# I2C_switch.net
KiCad netlist of a schematic drawn in Altium Designer
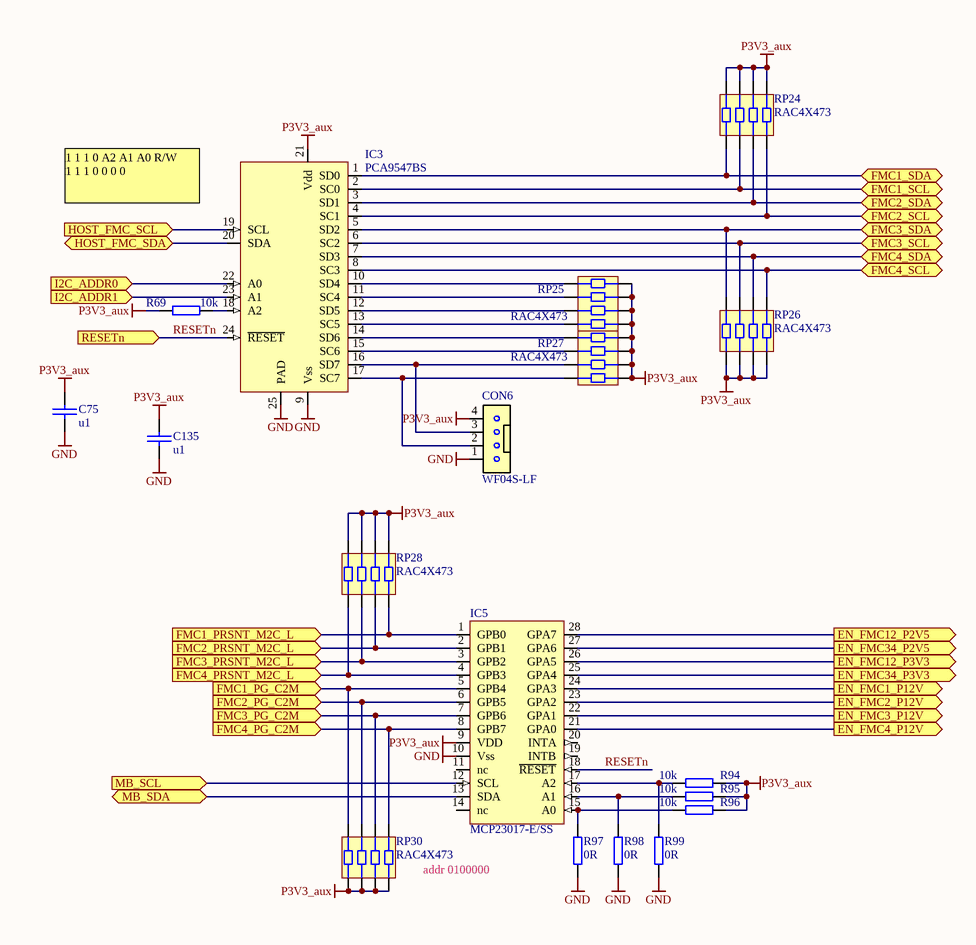
[diagram p0: I2C switch.SchDoc]

(export (version "E")
  (design (tool "Eeschema 10.0.6"))
  (components
    (comp (ref "C75")
      (value "u1")
      (footprint "0402C")
      (description "Capacitor SMD")
      (libsource (lib "LIBRARY_SCH") (part "CAP_SMD"))
    )
    (comp (ref "C135")
      (value "u1")
      (footprint "0402C")
      (description "Capacitor SMD")
      (libsource (lib "LIBRARY_SCH") (part "CAP_SMD"))
    )
    (comp (ref "CON6")
      (value "WF04S-LF")
      (footprint "CON_WF04S-LF")
      (libsource (lib "LIBRARY_SCH") (part "CON_4_2.54_key"))
    )
    (comp (ref "IC3")
      (value "PCA9547BS")
      (footprint "HVQFN24")
      (description "8-channel I2C-bus multiplexer with reset")
      (libsource (lib "LIBRARY_SCH") (part "IIC_MUX_PCA9547"))
    )
    (comp (ref "IC5")
      (value "MCP23017-E/SS")
      (footprint "SSOP28")
      (description "16 bit I2C expander")
      (libsource (lib "LIBRARY_SCH") (part "IIC_MCP23017"))
    )
    (comp (ref "R69")
      (value "10k")
      (footprint "0402R")
      (description "SMD Resistor")
      (libsource (lib "LIBRARY_SCH") (part "RES_0402"))
    )
    (comp (ref "R94")
      (value "10k")
      (footprint "0402R")
      (description "SMD Resistor")
      (libsource (lib "LIBRARY_SCH") (part "RES_0603"))
    )
    (comp (ref "R95")
      (value "10k")
      (footprint "0402R")
      (description "SMD Resistor")
      (libsource (lib "LIBRARY_SCH") (part "RES_0603"))
    )
    (comp (ref "R96")
      (value "10k")
      (footprint "0402R")
      (description "SMD Resistor")
      (libsource (lib "LIBRARY_SCH") (part "RES_0603"))
    )
    (comp (ref "R97")
      (value "0R")
      (footprint "0603R")
      (description "SMD Resistor")
      (libsource (lib "LIBRARY_SCH") (part "RES_0402"))
    )
    (comp (ref "R98")
      (value "0R")
      (footprint "0603R")
      (description "SMD Resistor")
      (libsource (lib "LIBRARY_SCH") (part "RES_0402"))
    )
    (comp (ref "R99")
      (value "0R")
      (footprint "0603R")
      (description "SMD Resistor")
      (libsource (lib "LIBRARY_SCH") (part "RES_0402"))
    )
    (comp (ref "RP24")
      (value "RAC4X473")
      (footprint "CAY-16")
      (description "Resistor network 1206 (4x0402) Maritex RAC4Xxxx")
      (libsource (lib "*") (part "RES_ARRAY_1206"))
    )
    (comp (ref "RP25")
      (value "RAC4X473")
      (footprint "CAY-16")
      (description "Resistor network 1206 (4x0402) Maritex RAC4Xxxx")
      (libsource (lib "") (part "RES_ARRAY_1206_1"))
    )
    (comp (ref "RP26")
      (value "RAC4X473")
      (footprint "CAY-16")
      (description "Resistor network 1206 (4x0402) Maritex RAC4Xxxx")
      (libsource (lib "") (part "RES_ARRAY_1206_1"))
    )
    (comp (ref "RP27")
      (value "RAC4X473")
      (footprint "CAY-16")
      (description "Resistor network 1206 (4x0402) Maritex RAC4Xxxx")
      (libsource (lib "") (part "RES_ARRAY_1206_1"))
    )
    (comp (ref "RP28")
      (value "RAC4X473")
      (footprint "CAY-16")
      (description "Resistor network 1206 (4x0402) Maritex RAC4Xxxx")
      (libsource (lib "") (part "RES_ARRAY_1206_1"))
    )
    (comp (ref "RP30")
      (value "RAC4X473")
      (footprint "CAY-16")
      (description "Resistor network 1206 (4x0402) Maritex RAC4Xxxx")
      (libsource (lib "") (part "RES_ARRAY_1206_2"))
    )
  )
  (nets
    (net (code "1") (name "/EN_FMC1_P12V") (class "Default")
      (node (ref "IC5") (pin "24") (pinfunction "GPA3_24") (pintype "bidirectional"))
    )
    (net (code "2") (name "/EN_FMC2_P12V") (class "Default")
      (node (ref "IC5") (pin "23") (pinfunction "GPA2_23") (pintype "bidirectional"))
    )
    (net (code "3") (name "/EN_FMC3_P12V") (class "Default")
      (node (ref "IC5") (pin "22") (pinfunction "GPA1_22") (pintype "bidirectional"))
    )
    (net (code "4") (name "/EN_FMC4_P12V") (class "Default")
      (node (ref "IC5") (pin "21") (pinfunction "GPA0_21") (pintype "bidirectional"))
    )
    (net (code "5") (name "/EN_FMC12_P2V5") (class "Default")
      (node (ref "IC5") (pin "28") (pinfunction "GPA7_28") (pintype "bidirectional"))
    )
    (net (code "6") (name "/EN_FMC12_P3V3") (class "Default")
      (node (ref "IC5") (pin "26") (pinfunction "GPA5_26") (pintype "bidirectional"))
    )
    (net (code "7") (name "/EN_FMC34_P2V5") (class "Default")
      (node (ref "IC5") (pin "27") (pinfunction "GPA6_27") (pintype "bidirectional"))
    )
    (net (code "8") (name "/EN_FMC34_P3V3") (class "Default")
      (node (ref "IC5") (pin "25") (pinfunction "GPA4_25") (pintype "bidirectional"))
    )
    (net (code "9") (name "/FMC1_PG_C2M") (class "Default")
      (node (ref "IC5") (pin "5") (pinfunction "GPB4_5") (pintype "bidirectional"))
      (node (ref "RP30") (pin "4") (pinfunction "4_4") (pintype "passive"))
    )
    (net (code "10") (name "/FMC1_PRSNT_M2C_L") (class "Default")
      (node (ref "IC5") (pin "1") (pinfunction "GPB0_1") (pintype "bidirectional"))
      (node (ref "RP28") (pin "4") (pinfunction "4_4") (pintype "passive"))
    )
    (net (code "11") (name "/FMC1_SCL") (class "Default")
      (node (ref "IC3") (pin "2") (pinfunction "SC0_2") (pintype "bidirectional"))
      (node (ref "RP24") (pin "7") (pinfunction "7_7") (pintype "passive"))
    )
    (net (code "12") (name "/FMC1_SDA") (class "Default")
      (node (ref "IC3") (pin "1") (pinfunction "SD0_1") (pintype "bidirectional"))
      (node (ref "RP24") (pin "8") (pinfunction "8_8") (pintype "passive"))
    )
    (net (code "13") (name "/FMC2_PG_C2M") (class "Default")
      (node (ref "IC5") (pin "6") (pinfunction "GPB5_6") (pintype "bidirectional"))
      (node (ref "RP30") (pin "3") (pinfunction "3_3") (pintype "passive"))
    )
    (net (code "14") (name "/FMC2_PRSNT_M2C_L") (class "Default")
      (node (ref "IC5") (pin "2") (pinfunction "GPB1_2") (pintype "bidirectional"))
      (node (ref "RP28") (pin "3") (pinfunction "3_3") (pintype "passive"))
    )
    (net (code "15") (name "/FMC2_SCL") (class "Default")
      (node (ref "IC3") (pin "4") (pinfunction "SC1_4") (pintype "bidirectional"))
      (node (ref "RP24") (pin "5") (pinfunction "5_5") (pintype "passive"))
    )
    (net (code "16") (name "/FMC2_SDA") (class "Default")
      (node (ref "IC3") (pin "3") (pinfunction "SD1_3") (pintype "bidirectional"))
      (node (ref "RP24") (pin "6") (pinfunction "6_6") (pintype "passive"))
    )
    (net (code "17") (name "/FMC3_PG_C2M") (class "Default")
      (node (ref "IC5") (pin "7") (pinfunction "GPB6_7") (pintype "bidirectional"))
      (node (ref "RP30") (pin "2") (pinfunction "2_2") (pintype "passive"))
    )
    (net (code "18") (name "/FMC3_PRSNT_M2C_L") (class "Default")
      (node (ref "IC5") (pin "3") (pinfunction "GPB2_3") (pintype "bidirectional"))
      (node (ref "RP28") (pin "2") (pinfunction "2_2") (pintype "passive"))
    )
    (net (code "19") (name "/FMC3_SCL") (class "Default")
      (node (ref "IC3") (pin "6") (pinfunction "SC2_6") (pintype "bidirectional"))
      (node (ref "RP26") (pin "7") (pinfunction "7_7") (pintype "passive"))
    )
    (net (code "20") (name "/FMC3_SDA") (class "Default")
      (node (ref "IC3") (pin "5") (pinfunction "SD2_5") (pintype "bidirectional"))
      (node (ref "RP26") (pin "8") (pinfunction "8_8") (pintype "passive"))
    )
    (net (code "21") (name "/FMC4_PG_C2M") (class "Default")
      (node (ref "IC5") (pin "8") (pinfunction "GPB7_8") (pintype "bidirectional"))
      (node (ref "RP30") (pin "1") (pinfunction "1_1") (pintype "passive"))
    )
    (net (code "22") (name "/FMC4_PRSNT_M2C_L") (class "Default")
      (node (ref "IC5") (pin "4") (pinfunction "GPB3_4") (pintype "bidirectional"))
      (node (ref "RP28") (pin "1") (pinfunction "1_1") (pintype "passive"))
    )
    (net (code "23") (name "/FMC4_SCL") (class "Default")
      (node (ref "IC3") (pin "8") (pinfunction "SC3_8") (pintype "bidirectional"))
      (node (ref "RP26") (pin "5") (pinfunction "5_5") (pintype "passive"))
    )
    (net (code "24") (name "/FMC4_SDA") (class "Default")
      (node (ref "IC3") (pin "7") (pinfunction "SD3_7") (pintype "bidirectional"))
      (node (ref "RP26") (pin "6") (pinfunction "6_6") (pintype "passive"))
    )
    (net (code "25") (name "/HOST_FMC_SCL") (class "Default")
      (node (ref "IC3") (pin "19") (pinfunction "SCL_19") (pintype "input"))
    )
    (net (code "26") (name "/HOST_FMC_SDA") (class "Default")
      (node (ref "IC3") (pin "20") (pinfunction "SDA_20") (pintype "bidirectional"))
    )
    (net (code "27") (name "/I2C_ADDR0") (class "Default")
      (node (ref "IC3") (pin "22") (pinfunction "A0_22") (pintype "input"))
    )
    (net (code "28") (name "/I2C_ADDR1") (class "Default")
      (node (ref "IC3") (pin "23") (pinfunction "A1_23") (pintype "input"))
    )
    (net (code "29") (name "/MB_SCL") (class "Default")
      (node (ref "IC5") (pin "12") (pinfunction "SCL_12") (pintype "input"))
    )
    (net (code "30") (name "/MB_SDA") (class "Default")
      (node (ref "IC5") (pin "13") (pinfunction "SDA_13") (pintype "bidirectional"))
    )
    (net (code "31") (name "/RESETn") (class "Default")
      (node (ref "IC3") (pin "24") (pinfunction "~{RESET}_24") (pintype "input"))
      (node (ref "IC5") (pin "18") (pinfunction "~{RESET}_18") (pintype "input"))
    )
    (net (code "32") (name "GND") (class "Default")
      (node (ref "C135") (pin "2") (pinfunction "2_2") (pintype "passive"))
      (node (ref "C75") (pin "2") (pinfunction "2_2") (pintype "passive"))
      (node (ref "CON6") (pin "1") (pinfunction "1_1") (pintype "bidirectional"))
      (node (ref "IC3") (pin "25") (pinfunction "PAD_25") (pintype "power_in"))
      (node (ref "IC3") (pin "9") (pinfunction "Vss_9") (pintype "power_in"))
      (node (ref "IC5") (pin "10") (pinfunction "Vss_10") (pintype "power_in"))
      (node (ref "R97") (pin "1") (pinfunction "1_1") (pintype "passive"))
      (node (ref "R98") (pin "1") (pinfunction "1_1") (pintype "passive"))
      (node (ref "R99") (pin "1") (pinfunction "1_1") (pintype "passive"))
    )
    (net (code "33") (name "Net-(IC3-A2)") (class "Default")
      (node (ref "IC3") (pin "18") (pinfunction "A2_18") (pintype "input"))
      (node (ref "R69") (pin "2") (pinfunction "2_2") (pintype "passive"))
    )
    (net (code "34") (name "Net-(IC3-SC4)") (class "Default")
      (node (ref "IC3") (pin "11") (pinfunction "SC4_11") (pintype "bidirectional"))
      (node (ref "RP25") (pin "3") (pinfunction "3_3") (pintype "passive"))
    )
    (net (code "35") (name "Net-(IC3-SC5)") (class "Default")
      (node (ref "IC3") (pin "13") (pinfunction "SC5_13") (pintype "bidirectional"))
      (node (ref "RP25") (pin "1") (pinfunction "1_1") (pintype "passive"))
    )
    (net (code "36") (name "Net-(IC3-SC6)") (class "Default")
      (node (ref "IC3") (pin "15") (pinfunction "SC6_15") (pintype "bidirectional"))
      (node (ref "RP27") (pin "3") (pinfunction "3_3") (pintype "passive"))
    )
    (net (code "37") (name "Net-(IC3-SC7)") (class "Default")
      (node (ref "CON6") (pin "2") (pinfunction "2_2") (pintype "bidirectional"))
      (node (ref "IC3") (pin "17") (pinfunction "SC7_17") (pintype "bidirectional"))
      (node (ref "RP27") (pin "1") (pinfunction "1_1") (pintype "passive"))
    )
    (net (code "38") (name "Net-(IC3-SD4)") (class "Default")
      (node (ref "IC3") (pin "10") (pinfunction "SD4_10") (pintype "bidirectional"))
      (node (ref "RP25") (pin "4") (pinfunction "4_4") (pintype "passive"))
    )
    (net (code "39") (name "Net-(IC3-SD5)") (class "Default")
      (node (ref "IC3") (pin "12") (pinfunction "SD5_12") (pintype "bidirectional"))
      (node (ref "RP25") (pin "2") (pinfunction "2_2") (pintype "passive"))
    )
    (net (code "40") (name "Net-(IC3-SD6)") (class "Default")
      (node (ref "IC3") (pin "14") (pinfunction "SD6_14") (pintype "bidirectional"))
      (node (ref "RP27") (pin "4") (pinfunction "4_4") (pintype "passive"))
    )
    (net (code "41") (name "Net-(IC3-SD7)") (class "Default")
      (node (ref "CON6") (pin "3") (pinfunction "3_3") (pintype "bidirectional"))
      (node (ref "IC3") (pin "16") (pinfunction "SD7_16") (pintype "bidirectional"))
      (node (ref "RP27") (pin "2") (pinfunction "2_2") (pintype "passive"))
    )
    (net (code "42") (name "Net-(IC5-A0)") (class "Default")
      (node (ref "IC5") (pin "15") (pinfunction "A0_15") (pintype "input"))
      (node (ref "R96") (pin "1") (pinfunction "1_1") (pintype "passive"))
      (node (ref "R97") (pin "2") (pinfunction "2_2") (pintype "passive"))
    )
    (net (code "43") (name "Net-(IC5-A1)") (class "Default")
      (node (ref "IC5") (pin "16") (pinfunction "A1_16") (pintype "input"))
      (node (ref "R95") (pin "1") (pinfunction "1_1") (pintype "passive"))
      (node (ref "R98") (pin "2") (pinfunction "2_2") (pintype "passive"))
    )
    (net (code "44") (name "Net-(IC5-A2)") (class "Default")
      (node (ref "IC5") (pin "17") (pinfunction "A2_17") (pintype "input"))
      (node (ref "R94") (pin "1") (pinfunction "1_1") (pintype "passive"))
      (node (ref "R99") (pin "2") (pinfunction "2_2") (pintype "passive"))
    )
    (net (code "45") (name "P3V3_aux") (class "Default")
      (node (ref "C135") (pin "1") (pinfunction "1_1") (pintype "passive"))
      (node (ref "C75") (pin "1") (pinfunction "1_1") (pintype "passive"))
      (node (ref "CON6") (pin "4") (pinfunction "4_4") (pintype "bidirectional"))
      (node (ref "IC3") (pin "21") (pinfunction "Vdd_21") (pintype "power_in"))
      (node (ref "IC5") (pin "9") (pinfunction "VDD_9") (pintype "power_in"))
      (node (ref "R69") (pin "1") (pinfunction "1_1") (pintype "passive"))
      (node (ref "R94") (pin "2") (pinfunction "2_2") (pintype "passive"))
      (node (ref "R95") (pin "2") (pinfunction "2_2") (pintype "passive"))
      (node (ref "R96") (pin "2") (pinfunction "2_2") (pintype "passive"))
      (node (ref "RP24") (pin "1") (pinfunction "1_1") (pintype "passive"))
      (node (ref "RP24") (pin "2") (pinfunction "2_2") (pintype "passive"))
      (node (ref "RP24") (pin "3") (pinfunction "3_3") (pintype "passive"))
      (node (ref "RP24") (pin "4") (pinfunction "4_4") (pintype "passive"))
      (node (ref "RP25") (pin "5") (pinfunction "5_5") (pintype "passive"))
      (node (ref "RP25") (pin "6") (pinfunction "6_6") (pintype "passive"))
      (node (ref "RP25") (pin "7") (pinfunction "7_7") (pintype "passive"))
      (node (ref "RP25") (pin "8") (pinfunction "8_8") (pintype "passive"))
      (node (ref "RP26") (pin "1") (pinfunction "1_1") (pintype "passive"))
      (node (ref "RP26") (pin "2") (pinfunction "2_2") (pintype "passive"))
      (node (ref "RP26") (pin "3") (pinfunction "3_3") (pintype "passive"))
      (node (ref "RP26") (pin "4") (pinfunction "4_4") (pintype "passive"))
      (node (ref "RP27") (pin "5") (pinfunction "5_5") (pintype "passive"))
      (node (ref "RP27") (pin "6") (pinfunction "6_6") (pintype "passive"))
      (node (ref "RP27") (pin "7") (pinfunction "7_7") (pintype "passive"))
      (node (ref "RP27") (pin "8") (pinfunction "8_8") (pintype "passive"))
      (node (ref "RP28") (pin "5") (pinfunction "5_5") (pintype "passive"))
      (node (ref "RP28") (pin "6") (pinfunction "6_6") (pintype "passive"))
      (node (ref "RP28") (pin "7") (pinfunction "7_7") (pintype "passive"))
      (node (ref "RP28") (pin "8") (pinfunction "8_8") (pintype "passive"))
      (node (ref "RP30") (pin "5") (pinfunction "5_5") (pintype "passive"))
      (node (ref "RP30") (pin "6") (pinfunction "6_6") (pintype "passive"))
      (node (ref "RP30") (pin "7") (pinfunction "7_7") (pintype "passive"))
      (node (ref "RP30") (pin "8") (pinfunction "8_8") (pintype "passive"))
    )
    (net (code "46") (name "unconnected-(IC5-INTA-Pad20)") (class "Default")
      (node (ref "IC5") (pin "20") (pinfunction "INTA_20") (pintype "output"))
    )
    (net (code "47") (name "unconnected-(IC5-INTB-Pad19)") (class "Default")
      (node (ref "IC5") (pin "19") (pinfunction "INTB_19") (pintype "output"))
    )
    (net (code "48") (name "unconnected-(IC5-nc-Pad11)") (class "Default")
      (node (ref "IC5") (pin "11") (pinfunction "nc_11") (pintype "power_in"))
    )
    (net (code "49") (name "unconnected-(IC5-nc-Pad14)") (class "Default")
      (node (ref "IC5") (pin "14") (pinfunction "nc_14") (pintype "passive"))
    )
  )
)
